# op-synth_0_91.net
KiCad netlist of a schematic drawn in EAGLE
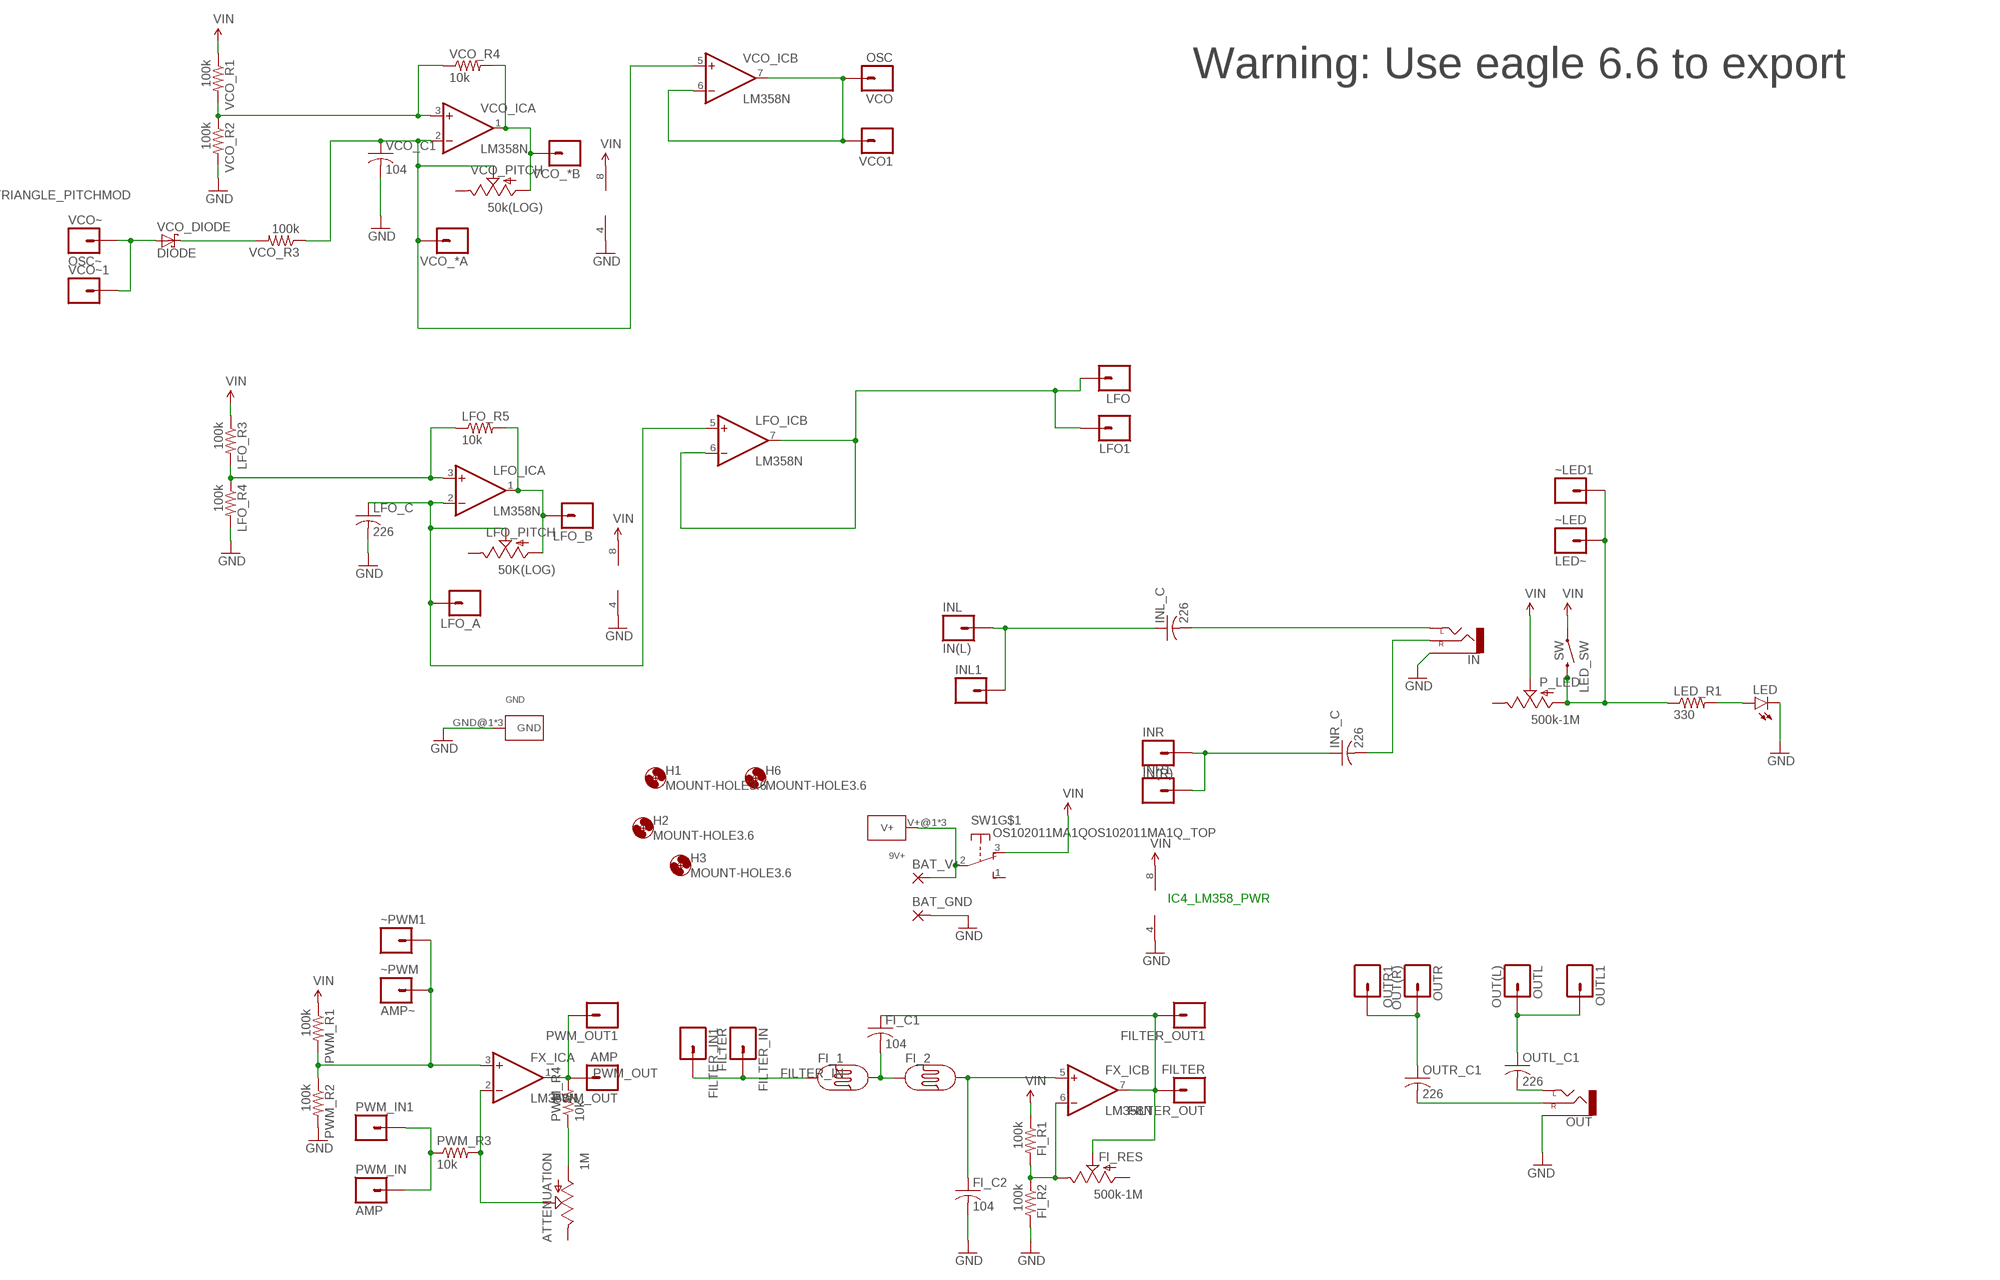
[diagram p0: schematic, sheet 1]

(export (version "E")
  (design (tool "Eeschema 10.0.6"))
  (components
    (comp (ref "9V+")
      (value "KEYSTONE-629+")
      (footprint "eagle-import:KEYSTONE_BATTAERY_TERMINAL-629+")
      (libsource (lib "eagle-import") (part "KEYSTONE-629+"))
    )
    (comp (ref "ATTENUATION")
      (value "1M")
      (footprint "eagle-import:TRIM_POT")
      (libsource (lib "eagle-import") (part "POTTRIM"))
    )
    (comp (ref "BAT_GND")
      (value "3,81/1,4")
      (footprint "eagle-import:3,81_1,4")
      (libsource (lib "eagle-import") (part "3,81/1,4"))
    )
    (comp (ref "BAT_V+")
      (value "3,81/1,4")
      (footprint "eagle-import:3,81_1,4")
      (libsource (lib "eagle-import") (part "3,81/1,4"))
    )
    (comp (ref "FILTER_IN")
      (value "FILTER")
      (footprint "eagle-import:1X01_SIDE_NAME")
      (libsource (lib "eagle-import") (part "HEADER-1X1"))
    )
    (comp (ref "FILTER_IN1")
      (value "HEADER-1X1")
      (footprint "eagle-import:1X01_SIDE_NAME")
      (libsource (lib "eagle-import") (part "HEADER-1X1"))
    )
    (comp (ref "FILTER_OUT")
      (value "FILTER")
      (footprint "eagle-import:1X01_SIDE_NAME")
      (libsource (lib "eagle-import") (part "HEADER-1X1"))
    )
    (comp (ref "FILTER_OUT1")
      (value "HEADER-1X1")
      (footprint "eagle-import:1X01_SIDE_NAME")
      (libsource (lib "eagle-import") (part "HEADER-1X1"))
    )
    (comp (ref "FI_1")
      (value "PHOTOCELLPTH")
      (footprint "eagle-import:PHOTOCELL")
      (libsource (lib "eagle-import") (part "PHOTOCELLPTH"))
    )
    (comp (ref "FI_2")
      (value "PHOTOCELLPTH")
      (footprint "eagle-import:PHOTOCELL")
      (libsource (lib "eagle-import") (part "PHOTOCELLPTH"))
    )
    (comp (ref "FI_C1")
      (value "104")
      (footprint "eagle-import:C050-024X044")
      (libsource (lib "eagle-import") (part "resistor_C-US050-024X044"))
    )
    (comp (ref "FI_C2")
      (value "104")
      (footprint "eagle-import:C050-024X044")
      (libsource (lib "eagle-import") (part "resistor_C-US050-024X044"))
    )
    (comp (ref "FI_R1")
      (value "100k")
      (footprint "eagle-import:0204_7")
      (libsource (lib "eagle-import") (part "R-US_0204/7"))
    )
    (comp (ref "FI_R2")
      (value "100k")
      (footprint "eagle-import:0204_7")
      (libsource (lib "eagle-import") (part "R-US_0204/7"))
    )
    (comp (ref "FI_RES")
      (value "500k-1M")
      (footprint "eagle-import:ALPS_POT")
      (libsource (lib "eagle-import") (part "POT"))
    )
    (comp (ref "FX_IC")
      (value "LM358N")
      (footprint "eagle-import:DIL08")
      (libsource (lib "eagle-import") (part "LM358N"))
    )
    (comp (ref "GND")
      (value "KEYSTONE-629")
      (footprint "eagle-import:KEYSTONE_AA_AAA_BATTERY_TERMINAL-629")
      (libsource (lib "eagle-import") (part "KEYSTONE-629"))
    )
    (comp (ref "H1")
      (value "MOUNT-HOLE3.6")
      (footprint "eagle-import:3,6")
      (libsource (lib "eagle-import") (part "MOUNT-HOLE3.6"))
    )
    (comp (ref "H2")
      (value "MOUNT-HOLE3.6")
      (footprint "eagle-import:3,6")
      (libsource (lib "eagle-import") (part "MOUNT-HOLE3.6"))
    )
    (comp (ref "H3")
      (value "MOUNT-HOLE3.6")
      (footprint "eagle-import:3,6")
      (libsource (lib "eagle-import") (part "MOUNT-HOLE3.6"))
    )
    (comp (ref "H6")
      (value "MOUNT-HOLE3.6")
      (footprint "eagle-import:3,6")
      (libsource (lib "eagle-import") (part "MOUNT-HOLE3.6"))
    )
    (comp (ref "IN")
      (value "AUDIO-JACKPTH")
      (footprint "eagle-import:AUDIO-JACK")
      (libsource (lib "eagle-import") (part "AUDIO-JACKPTH"))
    )
    (comp (ref "INL")
      (value "IN(L)")
      (footprint "eagle-import:1X01_SIDE_NAME")
      (libsource (lib "eagle-import") (part "HEADER-1X1"))
    )
    (comp (ref "INL1")
      (value "HEADER-1X1")
      (footprint "eagle-import:1X01_SIDE_NAME")
      (libsource (lib "eagle-import") (part "HEADER-1X1"))
    )
    (comp (ref "INL_C")
      (value "226")
      (footprint "eagle-import:C050-024X044")
      (libsource (lib "eagle-import") (part "C-US050-024X044"))
    )
    (comp (ref "INR")
      (value "IN(R)")
      (footprint "eagle-import:1X01_SIDE_NAME")
      (libsource (lib "eagle-import") (part "HEADER-1X1"))
    )
    (comp (ref "INR1")
      (value "HEADER-1X1")
      (footprint "eagle-import:1X01_SIDE_NAME")
      (libsource (lib "eagle-import") (part "HEADER-1X1"))
    )
    (comp (ref "INR_C")
      (value "226")
      (footprint "eagle-import:C050-024X044")
      (libsource (lib "eagle-import") (part "C-US050-024X044"))
    )
    (comp (ref "LED")
      (value "LED5MM")
      (footprint "eagle-import:LED5MM")
      (libsource (lib "eagle-import") (part "LED5MM"))
    )
    (comp (ref "LED_R1")
      (value "330")
      (footprint "eagle-import:0204_7")
      (libsource (lib "eagle-import") (part "R-US_0204/7"))
    )
    (comp (ref "LED_SW")
      (value "SW")
      (footprint "eagle-import:TACTILE-PTH-12MM")
      (libsource (lib "eagle-import") (part "SWITCH-MOMENTARY-212MM"))
    )
    (comp (ref "LFO")
      (value "HEADER-1X1")
      (footprint "eagle-import:1X01_SIDE_NAME")
      (libsource (lib "eagle-import") (part "HEADER-1X1"))
    )
    (comp (ref "LFO1")
      (value "HEADER-1X1")
      (footprint "eagle-import:1X01_SIDE_NAME")
      (libsource (lib "eagle-import") (part "HEADER-1X1"))
    )
    (comp (ref "LFO_A")
      (value "HEADER-1X1")
      (footprint "eagle-import:1X01_SIDE_NAME")
      (libsource (lib "eagle-import") (part "HEADER-1X1"))
    )
    (comp (ref "LFO_B")
      (value "HEADER-1X1")
      (footprint "eagle-import:1X01_SIDE_NAME")
      (libsource (lib "eagle-import") (part "HEADER-1X1"))
    )
    (comp (ref "LFO_C")
      (value "226")
      (footprint "eagle-import:C050-024X044")
      (libsource (lib "eagle-import") (part "resistor_C-US050-024X044"))
    )
    (comp (ref "LFO_IC")
      (value "LM358N")
      (footprint "eagle-import:DIL08")
      (libsource (lib "eagle-import") (part "LM358N"))
    )
    (comp (ref "LFO_PITCH")
      (value "50K(LOG)")
      (footprint "eagle-import:ALPS_POT")
      (libsource (lib "eagle-import") (part "POT"))
    )
    (comp (ref "LFO_R3")
      (value "100k")
      (footprint "eagle-import:0204_7")
      (libsource (lib "eagle-import") (part "R-US_0204/7"))
    )
    (comp (ref "LFO_R4")
      (value "100k")
      (footprint "eagle-import:0204_7")
      (libsource (lib "eagle-import") (part "R-US_0204/7"))
    )
    (comp (ref "LFO_R5")
      (value "10k")
      (footprint "eagle-import:0204_7")
      (libsource (lib "eagle-import") (part "R-US_0204/7"))
    )
    (comp (ref "OUT")
      (value "AUDIO-JACKPTH")
      (footprint "eagle-import:AUDIO-JACK")
      (libsource (lib "eagle-import") (part "AUDIO-JACKPTH"))
    )
    (comp (ref "OUTL")
      (value "OUT(L)")
      (footprint "eagle-import:1X01_SIDE_NAME")
      (libsource (lib "eagle-import") (part "HEADER-1X1"))
    )
    (comp (ref "OUTL1")
      (value "HEADER-1X1")
      (footprint "eagle-import:1X01_SIDE_NAME")
      (libsource (lib "eagle-import") (part "HEADER-1X1"))
    )
    (comp (ref "OUTL_C1")
      (value "226")
      (footprint "eagle-import:C050-024X044")
      (libsource (lib "eagle-import") (part "C-US050-024X044"))
    )
    (comp (ref "OUTR")
      (value "OUT(R)")
      (footprint "eagle-import:1X01_SIDE_NAME")
      (libsource (lib "eagle-import") (part "HEADER-1X1"))
    )
    (comp (ref "OUTR1")
      (value "HEADER-1X1")
      (footprint "eagle-import:1X01_SIDE_NAME")
      (libsource (lib "eagle-import") (part "HEADER-1X1"))
    )
    (comp (ref "OUTR_C1")
      (value "226")
      (footprint "eagle-import:C050-024X044")
      (libsource (lib "eagle-import") (part "C-US050-024X044"))
    )
    (comp (ref "PWM_IN")
      (value "AMP")
      (footprint "eagle-import:1X01_SIDE_NAME")
      (libsource (lib "eagle-import") (part "HEADER-1X1"))
    )
    (comp (ref "PWM_IN1")
      (value "HEADER-1X1")
      (footprint "eagle-import:1X01_SIDE_NAME")
      (libsource (lib "eagle-import") (part "HEADER-1X1"))
    )
    (comp (ref "PWM_OUT")
      (value "AMP")
      (footprint "eagle-import:1X01_SIDE_NAME")
      (libsource (lib "eagle-import") (part "HEADER-1X1"))
    )
    (comp (ref "PWM_OUT1")
      (value "HEADER-1X1")
      (footprint "eagle-import:1X01_SIDE_NAME")
      (libsource (lib "eagle-import") (part "HEADER-1X1"))
    )
    (comp (ref "PWM_R1")
      (value "100k")
      (footprint "eagle-import:0204_7")
      (libsource (lib "eagle-import") (part "R-US_0204/7"))
    )
    (comp (ref "PWM_R2")
      (value "100k")
      (footprint "eagle-import:0204_7")
      (libsource (lib "eagle-import") (part "R-US_0204/7"))
    )
    (comp (ref "PWM_R3")
      (value "10k")
      (footprint "eagle-import:0204_7")
      (libsource (lib "eagle-import") (part "R-US_0204/7"))
    )
    (comp (ref "PWM_R4")
      (value "10k")
      (footprint "eagle-import:0204_7")
      (libsource (lib "eagle-import") (part "R-US_0204/7"))
    )
    (comp (ref "P_LED")
      (value "500k-1M")
      (footprint "eagle-import:ALPS_POT")
      (libsource (lib "eagle-import") (part "POT"))
    )
    (comp (ref "SW1")
      (value "OS102011MA1QOS102011MA1Q_TOP")
      (footprint "eagle-import:OS102011MA1Q")
      (libsource (lib "eagle-import") (part "OS102011MA1QOS102011MA1Q_TOP"))
    )
    (comp (ref "VCO")
      (value "OSC")
      (footprint "eagle-import:1X01_SIDE_NAME")
      (libsource (lib "eagle-import") (part "HEADER-1X1"))
    )
    (comp (ref "VCO1")
      (value "HEADER-1X1")
      (footprint "eagle-import:1X01_SIDE_NAME")
      (libsource (lib "eagle-import") (part "HEADER-1X1"))
    )
    (comp (ref "VCO_*A")
      (value "HEADER-1X1")
      (footprint "eagle-import:1X01_SIDE_NAME")
      (libsource (lib "eagle-import") (part "HEADER-1X1"))
    )
    (comp (ref "VCO_*B")
      (value "HEADER-1X1")
      (footprint "eagle-import:1X01_SIDE_NAME")
      (libsource (lib "eagle-import") (part "HEADER-1X1"))
    )
    (comp (ref "VCO_C1")
      (value "104")
      (footprint "eagle-import:C050-024X044")
      (libsource (lib "eagle-import") (part "C-US050-024X044"))
    )
    (comp (ref "VCO_DIODE")
      (value "DIODE")
      (footprint "eagle-import:DO41-7")
      (libsource (lib "eagle-import") (part "SCHOTTKY-DIODEDO41-7"))
    )
    (comp (ref "VCO_IC")
      (value "LM358N")
      (footprint "eagle-import:DIL08")
      (libsource (lib "eagle-import") (part "LM358N"))
    )
    (comp (ref "VCO_PITCH")
      (value "50k(LOG)")
      (footprint "eagle-import:ALPS_POT")
      (libsource (lib "eagle-import") (part "POT"))
    )
    (comp (ref "VCO_R1")
      (value "100k")
      (footprint "eagle-import:0204_7")
      (libsource (lib "eagle-import") (part "R-US_0204/7"))
    )
    (comp (ref "VCO_R2")
      (value "100k")
      (footprint "eagle-import:0204_7")
      (libsource (lib "eagle-import") (part "R-US_0204/7"))
    )
    (comp (ref "VCO_R3")
      (value "100k")
      (footprint "eagle-import:0204_7")
      (libsource (lib "eagle-import") (part "R-US_0204/7"))
    )
    (comp (ref "VCO_R4")
      (value "10k")
      (footprint "eagle-import:0204_7")
      (libsource (lib "eagle-import") (part "R-US_0204/7"))
    )
    (comp (ref "VCO~")
      (value "OSC~")
      (footprint "eagle-import:1X01_SIDE_NAME")
      (libsource (lib "eagle-import") (part "HEADER-1X1"))
    )
    (comp (ref "VCO~1")
      (value "HEADER-1X1")
      (footprint "eagle-import:1X01_SIDE_NAME")
      (libsource (lib "eagle-import") (part "HEADER-1X1"))
    )
    (comp (ref "~LED")
      (value "LED~")
      (footprint "eagle-import:1X01_SIDE_NAME")
      (libsource (lib "eagle-import") (part "HEADER-1X1"))
    )
    (comp (ref "~LED1")
      (value "HEADER-1X1")
      (footprint "eagle-import:1X01_SIDE_NAME")
      (libsource (lib "eagle-import") (part "HEADER-1X1"))
    )
    (comp (ref "~PWM")
      (value "AMP~")
      (footprint "eagle-import:1X01_SIDE_NAME")
      (libsource (lib "eagle-import") (part "HEADER-1X1"))
    )
    (comp (ref "~PWM1")
      (value "HEADER-1X1")
      (footprint "eagle-import:1X01_SIDE_NAME")
      (libsource (lib "eagle-import") (part "HEADER-1X1"))
    )
  )
  (nets
    (net (code "1") (name "/FILTER_IN") (class "Default")
      (node (ref "FILTER_IN") (pin "1") (pinfunction "1_1") (pintype "passive"))
      (node (ref "FILTER_IN1") (pin "1") (pinfunction "1_1") (pintype "passive"))
      (node (ref "FI_1") (pin "1") (pinfunction "P$1_1") (pintype "bidirectional"))
    )
    (net (code "2") (name "/PWM_OUT") (class "Default")
      (node (ref "FX_IC") (pin "1") (pinfunction "OUT_1") (pintype "output"))
      (node (ref "PWM_OUT") (pin "1") (pinfunction "1_1") (pintype "passive"))
      (node (ref "PWM_OUT1") (pin "1") (pinfunction "1_1") (pintype "passive"))
      (node (ref "PWM_R4") (pin "2") (pinfunction "2_2") (pintype "passive"))
    )
    (net (code "3") (name "/TRIANGLE_PITCHMOD") (class "Default")
      (node (ref "VCO_DIODE") (pin "A") (pinfunction "A_A") (pintype "passive"))
      (node (ref "VCO~") (pin "1") (pinfunction "1_1") (pintype "passive"))
      (node (ref "VCO~1") (pin "1") (pinfunction "1_1") (pintype "passive"))
    )
    (net (code "4") (name "GND") (class "Default")
      (node (ref "BAT_GND") (pin "1") (pinfunction "P_1") (pintype "passive"))
      (node (ref "FI_C2") (pin "2") (pinfunction "2_2") (pintype "passive"))
      (node (ref "FI_R2") (pin "2") (pinfunction "2_2") (pintype "passive"))
      (node (ref "FX_IC") (pin "4") (pinfunction "V-_4") (pintype "power_in"))
      (node (ref "GND") (pin "GND@1") (pinfunction "GND_GND@1") (pintype "power_in"))
      (node (ref "GND") (pin "GND@2") (pinfunction "GND_GND@2") (pintype "power_in"))
      (node (ref "GND") (pin "GND@3") (pinfunction "GND_GND@3") (pintype "power_in"))
      (node (ref "IN") (pin "SLEEVE") (pinfunction "SLEEVE_SLEEVE") (pintype "bidirectional"))
      (node (ref "LED") (pin "K") (pinfunction "C_K") (pintype "passive"))
      (node (ref "LFO_C") (pin "2") (pinfunction "2_2") (pintype "passive"))
      (node (ref "LFO_IC") (pin "4") (pinfunction "V-_4") (pintype "power_in"))
      (node (ref "LFO_R4") (pin "2") (pinfunction "2_2") (pintype "passive"))
      (node (ref "OUT") (pin "SLEEVE") (pinfunction "SLEEVE_SLEEVE") (pintype "bidirectional"))
      (node (ref "PWM_R2") (pin "2") (pinfunction "2_2") (pintype "passive"))
      (node (ref "VCO_C1") (pin "2") (pinfunction "2_2") (pintype "passive"))
      (node (ref "VCO_IC") (pin "4") (pinfunction "V-_4") (pintype "power_in"))
      (node (ref "VCO_R2") (pin "2") (pinfunction "2_2") (pintype "passive"))
    )
    (net (code "5") (name "Net-(ATTENUATION-A)") (class "Default")
      (node (ref "ATTENUATION") (pin "3") (pinfunction "A_3") (pintype "passive"))
      (node (ref "PWM_R4") (pin "1") (pinfunction "1_1") (pintype "passive"))
    )
    (net (code "6") (name "Net-(ATTENUATION-S)") (class "Default")
      (node (ref "ATTENUATION") (pin "1") (pinfunction "S_1") (pintype "passive"))
      (node (ref "FX_IC") (pin "2") (pinfunction "-IN_2") (pintype "input"))
      (node (ref "PWM_R3") (pin "2") (pinfunction "2_2") (pintype "passive"))
    )
    (net (code "7") (name "Net-(BAT_V+-P)") (class "Default")
      (node (ref "9V+") (pin "V+@1") (pinfunction "V+_V+@1") (pintype "power_in"))
      (node (ref "9V+") (pin "V+@2") (pinfunction "V+_V+@2") (pintype "power_in"))
      (node (ref "9V+") (pin "V+@3") (pinfunction "V+_V+@3") (pintype "power_in"))
      (node (ref "BAT_V+") (pin "1") (pinfunction "P_1") (pintype "passive"))
      (node (ref "SW1") (pin "2") (pinfunction "P_2") (pintype "passive"))
    )
    (net (code "8") (name "Net-(FI_1-P$2)") (class "Default")
      (node (ref "FI_1") (pin "2") (pinfunction "P$2_2") (pintype "bidirectional"))
      (node (ref "FI_2") (pin "1") (pinfunction "P$1_1") (pintype "bidirectional"))
      (node (ref "FI_C1") (pin "2") (pinfunction "2_2") (pintype "passive"))
    )
    (net (code "9") (name "Net-(FI_2-P$2)") (class "Default")
      (node (ref "FI_2") (pin "2") (pinfunction "P$2_2") (pintype "bidirectional"))
      (node (ref "FI_C2") (pin "1") (pinfunction "1_1") (pintype "passive"))
      (node (ref "FX_IC") (pin "5") (pinfunction "+IN_5") (pintype "input"))
    )
    (net (code "10") (name "Net-(FI_RES-E)") (class "Default")
      (node (ref "FI_R1") (pin "2") (pinfunction "2_2") (pintype "passive"))
      (node (ref "FI_R2") (pin "1") (pinfunction "1_1") (pintype "passive"))
      (node (ref "FI_RES") (pin "P$1") (pinfunction "E_P$1") (pintype "passive"))
      (node (ref "FX_IC") (pin "6") (pinfunction "-IN_6") (pintype "input"))
    )
    (net (code "11") (name "Net-(FI_RES-S)") (class "Default")
      (node (ref "FILTER_OUT") (pin "1") (pinfunction "1_1") (pintype "passive"))
      (node (ref "FILTER_OUT1") (pin "1") (pinfunction "1_1") (pintype "passive"))
      (node (ref "FI_C1") (pin "1") (pinfunction "1_1") (pintype "passive"))
      (node (ref "FI_RES") (pin "P$2") (pinfunction "S_P$2") (pintype "passive"))
      (node (ref "FX_IC") (pin "7") (pinfunction "OUT_7") (pintype "output"))
    )
    (net (code "12") (name "Net-(FX_ICA-+IN)") (class "Default")
      (node (ref "FX_IC") (pin "3") (pinfunction "+IN_3") (pintype "input"))
      (node (ref "PWM_R1") (pin "2") (pinfunction "2_2") (pintype "passive"))
      (node (ref "PWM_R2") (pin "1") (pinfunction "1_1") (pintype "passive"))
      (node (ref "~PWM") (pin "1") (pinfunction "1_1") (pintype "passive"))
      (node (ref "~PWM1") (pin "1") (pinfunction "1_1") (pintype "passive"))
    )
    (net (code "13") (name "Net-(IN-LEFT)") (class "Default")
      (node (ref "IN") (pin "TIP") (pinfunction "LEFT_TIP") (pintype "bidirectional"))
      (node (ref "INL_C") (pin "2") (pinfunction "2_2") (pintype "passive"))
    )
    (net (code "14") (name "Net-(IN-RIGHT)") (class "Default")
      (node (ref "IN") (pin "RING") (pinfunction "RIGHT_RING") (pintype "bidirectional"))
      (node (ref "INR_C") (pin "2") (pinfunction "2_2") (pintype "passive"))
    )
    (net (code "15") (name "Net-(INL-Pad1)") (class "Default")
      (node (ref "INL") (pin "1") (pinfunction "1_1") (pintype "passive"))
      (node (ref "INL1") (pin "1") (pinfunction "1_1") (pintype "passive"))
      (node (ref "INL_C") (pin "1") (pinfunction "1_1") (pintype "passive"))
    )
    (net (code "16") (name "Net-(INR-Pad1)") (class "Default")
      (node (ref "INR") (pin "1") (pinfunction "1_1") (pintype "passive"))
      (node (ref "INR1") (pin "1") (pinfunction "1_1") (pintype "passive"))
      (node (ref "INR_C") (pin "1") (pinfunction "1_1") (pintype "passive"))
    )
    (net (code "17") (name "Net-(LED-PadA)") (class "Default")
      (node (ref "LED") (pin "A") (pinfunction "A_A") (pintype "passive"))
      (node (ref "LED_R1") (pin "2") (pinfunction "2_2") (pintype "passive"))
    )
    (net (code "18") (name "Net-(LED_SW-2)") (class "Default")
      (node (ref "LED_R1") (pin "1") (pinfunction "1_1") (pintype "passive"))
      (node (ref "LED_SW") (pin "3") (pinfunction "2_3") (pintype "passive"))
      (node (ref "P_LED") (pin "P$3") (pinfunction "A_P$3") (pintype "passive"))
      (node (ref "~LED") (pin "1") (pinfunction "1_1") (pintype "passive"))
      (node (ref "~LED1") (pin "1") (pinfunction "1_1") (pintype "passive"))
    )
    (net (code "19") (name "Net-(LFO_ICA-+IN)") (class "Default")
      (node (ref "LFO_IC") (pin "3") (pinfunction "+IN_3") (pintype "input"))
      (node (ref "LFO_R3") (pin "2") (pinfunction "2_2") (pintype "passive"))
      (node (ref "LFO_R4") (pin "1") (pinfunction "1_1") (pintype "passive"))
      (node (ref "LFO_R5") (pin "1") (pinfunction "1_1") (pintype "passive"))
    )
    (net (code "20") (name "Net-(LFO_ICA--IN)") (class "Default")
      (node (ref "LFO_A") (pin "1") (pinfunction "1_1") (pintype "passive"))
      (node (ref "LFO_C") (pin "1") (pinfunction "1_1") (pintype "passive"))
      (node (ref "LFO_IC") (pin "2") (pinfunction "-IN_2") (pintype "input"))
      (node (ref "LFO_IC") (pin "5") (pinfunction "+IN_5") (pintype "input"))
      (node (ref "LFO_PITCH") (pin "P$2") (pinfunction "S_P$2") (pintype "passive"))
    )
    (net (code "21") (name "Net-(LFO_ICA-OUT)") (class "Default")
      (node (ref "LFO_B") (pin "1") (pinfunction "1_1") (pintype "passive"))
      (node (ref "LFO_IC") (pin "1") (pinfunction "OUT_1") (pintype "output"))
      (node (ref "LFO_PITCH") (pin "P$3") (pinfunction "A_P$3") (pintype "passive"))
      (node (ref "LFO_R5") (pin "2") (pinfunction "2_2") (pintype "passive"))
    )
    (net (code "22") (name "Net-(LFO_ICB--IN)") (class "Default")
      (node (ref "LFO") (pin "1") (pinfunction "1_1") (pintype "passive"))
      (node (ref "LFO1") (pin "1") (pinfunction "1_1") (pintype "passive"))
      (node (ref "LFO_IC") (pin "6") (pinfunction "-IN_6") (pintype "input"))
      (node (ref "LFO_IC") (pin "7") (pinfunction "OUT_7") (pintype "output"))
    )
    (net (code "23") (name "Net-(OUT-LEFT)") (class "Default")
      (node (ref "OUT") (pin "TIP") (pinfunction "LEFT_TIP") (pintype "bidirectional"))
      (node (ref "OUTL_C1") (pin "2") (pinfunction "2_2") (pintype "passive"))
    )
    (net (code "24") (name "Net-(OUT-RIGHT)") (class "Default")
      (node (ref "OUT") (pin "RING") (pinfunction "RIGHT_RING") (pintype "bidirectional"))
      (node (ref "OUTR_C1") (pin "2") (pinfunction "2_2") (pintype "passive"))
    )
    (net (code "25") (name "Net-(OUTL-Pad1)") (class "Default")
      (node (ref "OUTL") (pin "1") (pinfunction "1_1") (pintype "passive"))
      (node (ref "OUTL1") (pin "1") (pinfunction "1_1") (pintype "passive"))
      (node (ref "OUTL_C1") (pin "1") (pinfunction "1_1") (pintype "passive"))
    )
    (net (code "26") (name "Net-(OUTR-Pad1)") (class "Default")
      (node (ref "OUTR") (pin "1") (pinfunction "1_1") (pintype "passive"))
      (node (ref "OUTR1") (pin "1") (pinfunction "1_1") (pintype "passive"))
      (node (ref "OUTR_C1") (pin "1") (pinfunction "1_1") (pintype "passive"))
    )
    (net (code "27") (name "Net-(PWM_IN-Pad1)") (class "Default")
      (node (ref "PWM_IN") (pin "1") (pinfunction "1_1") (pintype "passive"))
      (node (ref "PWM_IN1") (pin "1") (pinfunction "1_1") (pintype "passive"))
      (node (ref "PWM_R3") (pin "1") (pinfunction "1_1") (pintype "passive"))
    )
    (net (code "28") (name "Net-(VCO_DIODE-PadC)") (class "Default")
      (node (ref "VCO_DIODE") (pin "C") (pinfunction "C_C") (pintype "passive"))
      (node (ref "VCO_R3") (pin "2") (pinfunction "2_2") (pintype "passive"))
    )
    (net (code "29") (name "Net-(VCO_ICA-+IN)") (class "Default")
      (node (ref "VCO_IC") (pin "3") (pinfunction "+IN_3") (pintype "input"))
      (node (ref "VCO_R1") (pin "2") (pinfunction "2_2") (pintype "passive"))
      (node (ref "VCO_R2") (pin "1") (pinfunction "1_1") (pintype "passive"))
      (node (ref "VCO_R4") (pin "1") (pinfunction "1_1") (pintype "passive"))
    )
    (net (code "30") (name "Net-(VCO_ICA--IN)") (class "Default")
      (node (ref "VCO_*A") (pin "1") (pinfunction "1_1") (pintype "passive"))
      (node (ref "VCO_C1") (pin "1") (pinfunction "1_1") (pintype "passive"))
      (node (ref "VCO_IC") (pin "2") (pinfunction "-IN_2") (pintype "input"))
      (node (ref "VCO_IC") (pin "5") (pinfunction "+IN_5") (pintype "input"))
      (node (ref "VCO_PITCH") (pin "P$2") (pinfunction "S_P$2") (pintype "passive"))
      (node (ref "VCO_R3") (pin "1") (pinfunction "1_1") (pintype "passive"))
    )
    (net (code "31") (name "Net-(VCO_ICA-OUT)") (class "Default")
      (node (ref "VCO_*B") (pin "1") (pinfunction "1_1") (pintype "passive"))
      (node (ref "VCO_IC") (pin "1") (pinfunction "OUT_1") (pintype "output"))
      (node (ref "VCO_PITCH") (pin "P$3") (pinfunction "A_P$3") (pintype "passive"))
      (node (ref "VCO_R4") (pin "2") (pinfunction "2_2") (pintype "passive"))
    )
    (net (code "32") (name "Net-(VCO_ICB--IN)") (class "Default")
      (node (ref "VCO") (pin "1") (pinfunction "1_1") (pintype "passive"))
      (node (ref "VCO1") (pin "1") (pinfunction "1_1") (pintype "passive"))
      (node (ref "VCO_IC") (pin "6") (pinfunction "-IN_6") (pintype "input"))
      (node (ref "VCO_IC") (pin "7") (pinfunction "OUT_7") (pintype "output"))
    )
    (net (code "33") (name "VIN") (class "Default")
      (node (ref "FI_R1") (pin "1") (pinfunction "1_1") (pintype "passive"))
      (node (ref "FX_IC") (pin "8") (pinfunction "V+_8") (pintype "power_in"))
      (node (ref "LED_SW") (pin "1") (pinfunction "1_1") (pintype "passive"))
      (node (ref "LFO_IC") (pin "8") (pinfunction "V+_8") (pintype "power_in"))
      (node (ref "LFO_R3") (pin "1") (pinfunction "1_1") (pintype "passive"))
      (node (ref "PWM_R1") (pin "1") (pinfunction "1_1") (pintype "passive"))
      (node (ref "P_LED") (pin "P$2") (pinfunction "S_P$2") (pintype "passive"))
      (node (ref "SW1") (pin "3") (pinfunction "O_3") (pintype "passive"))
      (node (ref "VCO_IC") (pin "8") (pinfunction "V+_8") (pintype "power_in"))
      (node (ref "VCO_R1") (pin "1") (pinfunction "1_1") (pintype "passive"))
    )
    (net (code "34") (name "unconnected-(ATTENUATION-E-Pad2)") (class "Default")
      (node (ref "ATTENUATION") (pin "2") (pinfunction "E_2") (pintype "passive"))
    )
    (net (code "35") (name "unconnected-(FI_RES-A-PadP$3)") (class "Default")
      (node (ref "FI_RES") (pin "P$3") (pinfunction "A_P$3") (pintype "passive"))
    )
    (net (code "36") (name "unconnected-(LFO_PITCH-E-PadP$1)") (class "Default")
      (node (ref "LFO_PITCH") (pin "P$1") (pinfunction "E_P$1") (pintype "passive"))
    )
    (net (code "37") (name "unconnected-(P_LED-E-PadP$1)") (class "Default")
      (node (ref "P_LED") (pin "P$1") (pinfunction "E_P$1") (pintype "passive"))
    )
    (net (code "38") (name "unconnected-(SW1A-S-Pad1)") (class "Default")
      (node (ref "SW1") (pin "1") (pinfunction "S_1") (pintype "passive"))
    )
    (net (code "39") (name "unconnected-(VCO_PITCH-E-PadP$1)") (class "Default")
      (node (ref "VCO_PITCH") (pin "P$1") (pinfunction "E_P$1") (pintype "passive"))
    )
  )
)
